# MCU_STM32.net
KiCad netlist of a schematic drawn in Altium Designer
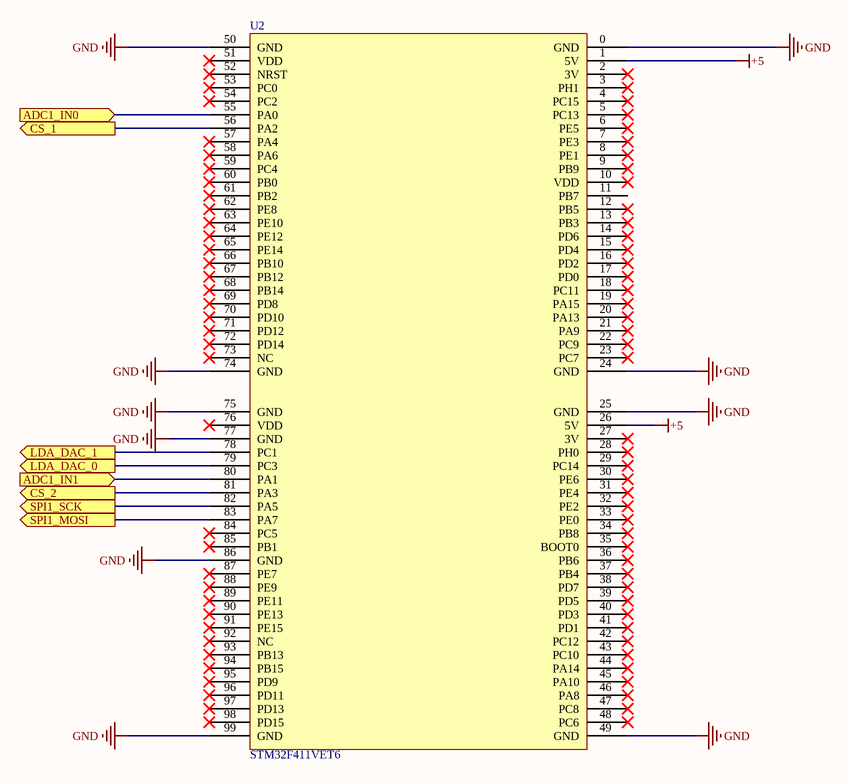
[diagram p0: MCU_STM32.SchDoc]

(export (version "E")
  (design (tool "Eeschema 10.0.6"))
  (components
    (comp (ref "U2")
      (value "STM32F411VET6")
      (footprint "STM32F4")
      (libsource (lib "Iot_Flatform_lib_PTT") (part "STM32F411VET6"))
    )
  )
  (nets
    (net (code "1") (name "+5") (class "Default")
      (node (ref "U2") (pin "1") (pinfunction "5V_1") (pintype "passive"))
      (node (ref "U2") (pin "26") (pinfunction "5V_26") (pintype "passive"))
    )
    (net (code "2") (name "/ADC1_IN0") (class "Default")
      (node (ref "U2") (pin "55") (pinfunction "PA0_55") (pintype "passive"))
    )
    (net (code "3") (name "/ADC1_IN1") (class "Default")
      (node (ref "U2") (pin "80") (pinfunction "PA1_80") (pintype "passive"))
    )
    (net (code "4") (name "/CS_1") (class "Default")
      (node (ref "U2") (pin "56") (pinfunction "PA2_56") (pintype "passive"))
    )
    (net (code "5") (name "/CS_2") (class "Default")
      (node (ref "U2") (pin "81") (pinfunction "PA3_81") (pintype "passive"))
    )
    (net (code "6") (name "/LDA_DAC_0") (class "Default")
      (node (ref "U2") (pin "79") (pinfunction "PC3_79") (pintype "passive"))
    )
    (net (code "7") (name "/LDA_DAC_1") (class "Default")
      (node (ref "U2") (pin "78") (pinfunction "PC1_78") (pintype "passive"))
    )
    (net (code "8") (name "/SPI1_MOSI") (class "Default")
      (node (ref "U2") (pin "83") (pinfunction "PA7_83") (pintype "passive"))
    )
    (net (code "9") (name "/SPI1_SCK") (class "Default")
      (node (ref "U2") (pin "82") (pinfunction "PA5_82") (pintype "passive"))
    )
    (net (code "10") (name "GND") (class "Default")
      (node (ref "U2") (pin "0") (pinfunction "GND_0") (pintype "passive"))
      (node (ref "U2") (pin "24") (pinfunction "GND_24") (pintype "passive"))
      (node (ref "U2") (pin "25") (pinfunction "GND_25") (pintype "passive"))
      (node (ref "U2") (pin "49") (pinfunction "GND_49") (pintype "passive"))
      (node (ref "U2") (pin "50") (pinfunction "GND_50") (pintype "passive"))
      (node (ref "U2") (pin "74") (pinfunction "GND_74") (pintype "passive"))
      (node (ref "U2") (pin "75") (pinfunction "GND_75") (pintype "passive"))
      (node (ref "U2") (pin "77") (pinfunction "GND_77") (pintype "passive"))
      (node (ref "U2") (pin "86") (pinfunction "GND_86") (pintype "passive"))
      (node (ref "U2") (pin "99") (pinfunction "GND_99") (pintype "passive"))
    )
    (net (code "11") (name "unconnected-(U2-3V-Pad2)") (class "Default")
      (node (ref "U2") (pin "2") (pinfunction "3V_2") (pintype "passive+no_connect"))
    )
    (net (code "12") (name "unconnected-(U2-3V-Pad27)") (class "Default")
      (node (ref "U2") (pin "27") (pinfunction "3V_27") (pintype "passive+no_connect"))
    )
    (net (code "13") (name "unconnected-(U2-BOOT0-Pad35)") (class "Default")
      (node (ref "U2") (pin "35") (pinfunction "BOOT0_35") (pintype "passive+no_connect"))
    )
    (net (code "14") (name "unconnected-(U2-NC-Pad73)") (class "Default")
      (node (ref "U2") (pin "73") (pinfunction "NC_73") (pintype "passive+no_connect"))
    )
    (net (code "15") (name "unconnected-(U2-NC-Pad92)") (class "Default")
      (node (ref "U2") (pin "92") (pinfunction "NC_92") (pintype "passive+no_connect"))
    )
    (net (code "16") (name "unconnected-(U2-NRST-Pad52)") (class "Default")
      (node (ref "U2") (pin "52") (pinfunction "NRST_52") (pintype "passive+no_connect"))
    )
    (net (code "17") (name "unconnected-(U2-PA4-Pad57)") (class "Default")
      (node (ref "U2") (pin "57") (pinfunction "PA4_57") (pintype "passive+no_connect"))
    )
    (net (code "18") (name "unconnected-(U2-PA6-Pad58)") (class "Default")
      (node (ref "U2") (pin "58") (pinfunction "PA6_58") (pintype "passive+no_connect"))
    )
    (net (code "19") (name "unconnected-(U2-PA8-Pad46)") (class "Default")
      (node (ref "U2") (pin "46") (pinfunction "PA8_46") (pintype "passive+no_connect"))
    )
    (net (code "20") (name "unconnected-(U2-PA9-Pad21)") (class "Default")
      (node (ref "U2") (pin "21") (pinfunction "PA9_21") (pintype "passive+no_connect"))
    )
    (net (code "21") (name "unconnected-(U2-PA10-Pad45)") (class "Default")
      (node (ref "U2") (pin "45") (pinfunction "PA10_45") (pintype "passive+no_connect"))
    )
    (net (code "22") (name "unconnected-(U2-PA13-Pad20)") (class "Default")
      (node (ref "U2") (pin "20") (pinfunction "PA13_20") (pintype "passive+no_connect"))
    )
    (net (code "23") (name "unconnected-(U2-PA14-Pad44)") (class "Default")
      (node (ref "U2") (pin "44") (pinfunction "PA14_44") (pintype "passive+no_connect"))
    )
    (net (code "24") (name "unconnected-(U2-PA15-Pad19)") (class "Default")
      (node (ref "U2") (pin "19") (pinfunction "PA15_19") (pintype "passive+no_connect"))
    )
    (net (code "25") (name "unconnected-(U2-PB0-Pad60)") (class "Default")
      (node (ref "U2") (pin "60") (pinfunction "PB0_60") (pintype "passive+no_connect"))
    )
    (net (code "26") (name "unconnected-(U2-PB1-Pad85)") (class "Default")
      (node (ref "U2") (pin "85") (pinfunction "PB1_85") (pintype "passive+no_connect"))
    )
    (net (code "27") (name "unconnected-(U2-PB2-Pad61)") (class "Default")
      (node (ref "U2") (pin "61") (pinfunction "PB2_61") (pintype "passive+no_connect"))
    )
    (net (code "28") (name "unconnected-(U2-PB3-Pad13)") (class "Default")
      (node (ref "U2") (pin "13") (pinfunction "PB3_13") (pintype "passive+no_connect"))
    )
    (net (code "29") (name "unconnected-(U2-PB4-Pad37)") (class "Default")
      (node (ref "U2") (pin "37") (pinfunction "PB4_37") (pintype "passive+no_connect"))
    )
    (net (code "30") (name "unconnected-(U2-PB5-Pad12)") (class "Default")
      (node (ref "U2") (pin "12") (pinfunction "PB5_12") (pintype "passive+no_connect"))
    )
    (net (code "31") (name "unconnected-(U2-PB6-Pad36)") (class "Default")
      (node (ref "U2") (pin "36") (pinfunction "PB6_36") (pintype "passive+no_connect"))
    )
    (net (code "32") (name "unconnected-(U2-PB7-Pad11)") (class "Default")
      (node (ref "U2") (pin "11") (pinfunction "PB7_11") (pintype "passive"))
    )
    (net (code "33") (name "unconnected-(U2-PB8-Pad34)") (class "Default")
      (node (ref "U2") (pin "34") (pinfunction "PB8_34") (pintype "passive+no_connect"))
    )
    (net (code "34") (name "unconnected-(U2-PB9-Pad9)") (class "Default")
      (node (ref "U2") (pin "9") (pinfunction "PB9_9") (pintype "passive+no_connect"))
    )
    (net (code "35") (name "unconnected-(U2-PB10-Pad66)") (class "Default")
      (node (ref "U2") (pin "66") (pinfunction "PB10_66") (pintype "passive+no_connect"))
    )
    (net (code "36") (name "unconnected-(U2-PB12-Pad67)") (class "Default")
      (node (ref "U2") (pin "67") (pinfunction "PB12_67") (pintype "passive+no_connect"))
    )
    (net (code "37") (name "unconnected-(U2-PB13-Pad93)") (class "Default")
      (node (ref "U2") (pin "93") (pinfunction "PB13_93") (pintype "passive+no_connect"))
    )
    (net (code "38") (name "unconnected-(U2-PB14-Pad68)") (class "Default")
      (node (ref "U2") (pin "68") (pinfunction "PB14_68") (pintype "passive+no_connect"))
    )
    (net (code "39") (name "unconnected-(U2-PB15-Pad94)") (class "Default")
      (node (ref "U2") (pin "94") (pinfunction "PB15_94") (pintype "passive+no_connect"))
    )
    (net (code "40") (name "unconnected-(U2-PC0-Pad53)") (class "Default")
      (node (ref "U2") (pin "53") (pinfunction "PC0_53") (pintype "passive+no_connect"))
    )
    (net (code "41") (name "unconnected-(U2-PC2-Pad54)") (class "Default")
      (node (ref "U2") (pin "54") (pinfunction "PC2_54") (pintype "passive+no_connect"))
    )
    (net (code "42") (name "unconnected-(U2-PC4-Pad59)") (class "Default")
      (node (ref "U2") (pin "59") (pinfunction "PC4_59") (pintype "passive+no_connect"))
    )
    (net (code "43") (name "unconnected-(U2-PC5-Pad84)") (class "Default")
      (node (ref "U2") (pin "84") (pinfunction "PC5_84") (pintype "passive+no_connect"))
    )
    (net (code "44") (name "unconnected-(U2-PC6-Pad48)") (class "Default")
      (node (ref "U2") (pin "48") (pinfunction "PC6_48") (pintype "passive+no_connect"))
    )
    (net (code "45") (name "unconnected-(U2-PC7-Pad23)") (class "Default")
      (node (ref "U2") (pin "23") (pinfunction "PC7_23") (pintype "passive+no_connect"))
    )
    (net (code "46") (name "unconnected-(U2-PC8-Pad47)") (class "Default")
      (node (ref "U2") (pin "47") (pinfunction "PC8_47") (pintype "passive+no_connect"))
    )
    (net (code "47") (name "unconnected-(U2-PC9-Pad22)") (class "Default")
      (node (ref "U2") (pin "22") (pinfunction "PC9_22") (pintype "passive+no_connect"))
    )
    (net (code "48") (name "unconnected-(U2-PC10-Pad43)") (class "Default")
      (node (ref "U2") (pin "43") (pinfunction "PC10_43") (pintype "passive+no_connect"))
    )
    (net (code "49") (name "unconnected-(U2-PC11-Pad18)") (class "Default")
      (node (ref "U2") (pin "18") (pinfunction "PC11_18") (pintype "passive+no_connect"))
    )
    (net (code "50") (name "unconnected-(U2-PC12-Pad42)") (class "Default")
      (node (ref "U2") (pin "42") (pinfunction "PC12_42") (pintype "passive+no_connect"))
    )
    (net (code "51") (name "unconnected-(U2-PC13-Pad5)") (class "Default")
      (node (ref "U2") (pin "5") (pinfunction "PC13_5") (pintype "passive+no_connect"))
    )
    (net (code "52") (name "unconnected-(U2-PC14-Pad29)") (class "Default")
      (node (ref "U2") (pin "29") (pinfunction "PC14_29") (pintype "passive+no_connect"))
    )
    (net (code "53") (name "unconnected-(U2-PC15-Pad4)") (class "Default")
      (node (ref "U2") (pin "4") (pinfunction "PC15_4") (pintype "passive+no_connect"))
    )
    (net (code "54") (name "unconnected-(U2-PD0-Pad17)") (class "Default")
      (node (ref "U2") (pin "17") (pinfunction "PD0_17") (pintype "passive+no_connect"))
    )
    (net (code "55") (name "unconnected-(U2-PD1-Pad41)") (class "Default")
      (node (ref "U2") (pin "41") (pinfunction "PD1_41") (pintype "passive+no_connect"))
    )
    (net (code "56") (name "unconnected-(U2-PD2-Pad16)") (class "Default")
      (node (ref "U2") (pin "16") (pinfunction "PD2_16") (pintype "passive+no_connect"))
    )
    (net (code "57") (name "unconnected-(U2-PD3-Pad40)") (class "Default")
      (node (ref "U2") (pin "40") (pinfunction "PD3_40") (pintype "passive+no_connect"))
    )
    (net (code "58") (name "unconnected-(U2-PD4-Pad15)") (class "Default")
      (node (ref "U2") (pin "15") (pinfunction "PD4_15") (pintype "passive+no_connect"))
    )
    (net (code "59") (name "unconnected-(U2-PD5-Pad39)") (class "Default")
      (node (ref "U2") (pin "39") (pinfunction "PD5_39") (pintype "passive+no_connect"))
    )
    (net (code "60") (name "unconnected-(U2-PD6-Pad14)") (class "Default")
      (node (ref "U2") (pin "14") (pinfunction "PD6_14") (pintype "passive+no_connect"))
    )
    (net (code "61") (name "unconnected-(U2-PD7-Pad38)") (class "Default")
      (node (ref "U2") (pin "38") (pinfunction "PD7_38") (pintype "passive+no_connect"))
    )
    (net (code "62") (name "unconnected-(U2-PD8-Pad69)") (class "Default")
      (node (ref "U2") (pin "69") (pinfunction "PD8_69") (pintype "passive+no_connect"))
    )
    (net (code "63") (name "unconnected-(U2-PD9-Pad95)") (class "Default")
      (node (ref "U2") (pin "95") (pinfunction "PD9_95") (pintype "passive+no_connect"))
    )
    (net (code "64") (name "unconnected-(U2-PD10-Pad70)") (class "Default")
      (node (ref "U2") (pin "70") (pinfunction "PD10_70") (pintype "passive+no_connect"))
    )
    (net (code "65") (name "unconnected-(U2-PD11-Pad96)") (class "Default")
      (node (ref "U2") (pin "96") (pinfunction "PD11_96") (pintype "passive+no_connect"))
    )
    (net (code "66") (name "unconnected-(U2-PD12-Pad71)") (class "Default")
      (node (ref "U2") (pin "71") (pinfunction "PD12_71") (pintype "passive+no_connect"))
    )
    (net (code "67") (name "unconnected-(U2-PD13-Pad97)") (class "Default")
      (node (ref "U2") (pin "97") (pinfunction "PD13_97") (pintype "passive+no_connect"))
    )
    (net (code "68") (name "unconnected-(U2-PD14-Pad72)") (class "Default")
      (node (ref "U2") (pin "72") (pinfunction "PD14_72") (pintype "passive+no_connect"))
    )
    (net (code "69") (name "unconnected-(U2-PD15-Pad98)") (class "Default")
      (node (ref "U2") (pin "98") (pinfunction "PD15_98") (pintype "passive+no_connect"))
    )
    (net (code "70") (name "unconnected-(U2-PE0-Pad33)") (class "Default")
      (node (ref "U2") (pin "33") (pinfunction "PE0_33") (pintype "passive+no_connect"))
    )
    (net (code "71") (name "unconnected-(U2-PE1-Pad8)") (class "Default")
      (node (ref "U2") (pin "8") (pinfunction "PE1_8") (pintype "passive+no_connect"))
    )
    (net (code "72") (name "unconnected-(U2-PE2-Pad32)") (class "Default")
      (node (ref "U2") (pin "32") (pinfunction "PE2_32") (pintype "passive+no_connect"))
    )
    (net (code "73") (name "unconnected-(U2-PE3-Pad7)") (class "Default")
      (node (ref "U2") (pin "7") (pinfunction "PE3_7") (pintype "passive+no_connect"))
    )
    (net (code "74") (name "unconnected-(U2-PE4-Pad31)") (class "Default")
      (node (ref "U2") (pin "31") (pinfunction "PE4_31") (pintype "passive+no_connect"))
    )
    (net (code "75") (name "unconnected-(U2-PE5-Pad6)") (class "Default")
      (node (ref "U2") (pin "6") (pinfunction "PE5_6") (pintype "passive+no_connect"))
    )
    (net (code "76") (name "unconnected-(U2-PE6-Pad30)") (class "Default")
      (node (ref "U2") (pin "30") (pinfunction "PE6_30") (pintype "passive+no_connect"))
    )
    (net (code "77") (name "unconnected-(U2-PE7-Pad87)") (class "Default")
      (node (ref "U2") (pin "87") (pinfunction "PE7_87") (pintype "passive+no_connect"))
    )
    (net (code "78") (name "unconnected-(U2-PE8-Pad62)") (class "Default")
      (node (ref "U2") (pin "62") (pinfunction "PE8_62") (pintype "passive+no_connect"))
    )
    (net (code "79") (name "unconnected-(U2-PE9-Pad88)") (class "Default")
      (node (ref "U2") (pin "88") (pinfunction "PE9_88") (pintype "passive+no_connect"))
    )
    (net (code "80") (name "unconnected-(U2-PE10-Pad63)") (class "Default")
      (node (ref "U2") (pin "63") (pinfunction "PE10_63") (pintype "passive+no_connect"))
    )
    (net (code "81") (name "unconnected-(U2-PE11-Pad89)") (class "Default")
      (node (ref "U2") (pin "89") (pinfunction "PE11_89") (pintype "passive+no_connect"))
    )
    (net (code "82") (name "unconnected-(U2-PE12-Pad64)") (class "Default")
      (node (ref "U2") (pin "64") (pinfunction "PE12_64") (pintype "passive+no_connect"))
    )
    (net (code "83") (name "unconnected-(U2-PE13-Pad90)") (class "Default")
      (node (ref "U2") (pin "90") (pinfunction "PE13_90") (pintype "passive+no_connect"))
    )
    (net (code "84") (name "unconnected-(U2-PE14-Pad65)") (class "Default")
      (node (ref "U2") (pin "65") (pinfunction "PE14_65") (pintype "passive+no_connect"))
    )
    (net (code "85") (name "unconnected-(U2-PE15-Pad91)") (class "Default")
      (node (ref "U2") (pin "91") (pinfunction "PE15_91") (pintype "passive+no_connect"))
    )
    (net (code "86") (name "unconnected-(U2-PH0-Pad28)") (class "Default")
      (node (ref "U2") (pin "28") (pinfunction "PH0_28") (pintype "passive+no_connect"))
    )
    (net (code "87") (name "unconnected-(U2-PH1-Pad3)") (class "Default")
      (node (ref "U2") (pin "3") (pinfunction "PH1_3") (pintype "passive+no_connect"))
    )
    (net (code "88") (name "unconnected-(U2-VDD-Pad10)") (class "Default")
      (node (ref "U2") (pin "10") (pinfunction "VDD_10") (pintype "passive+no_connect"))
    )
    (net (code "89") (name "unconnected-(U2-VDD-Pad51)") (class "Default")
      (node (ref "U2") (pin "51") (pinfunction "VDD_51") (pintype "passive+no_connect"))
    )
    (net (code "90") (name "unconnected-(U2-VDD-Pad76)") (class "Default")
      (node (ref "U2") (pin "76") (pinfunction "VDD_76") (pintype "passive+no_connect"))
    )
  )
)
